# PicoLED.net
KiCad netlist of a schematic drawn in EasyEDA Pro
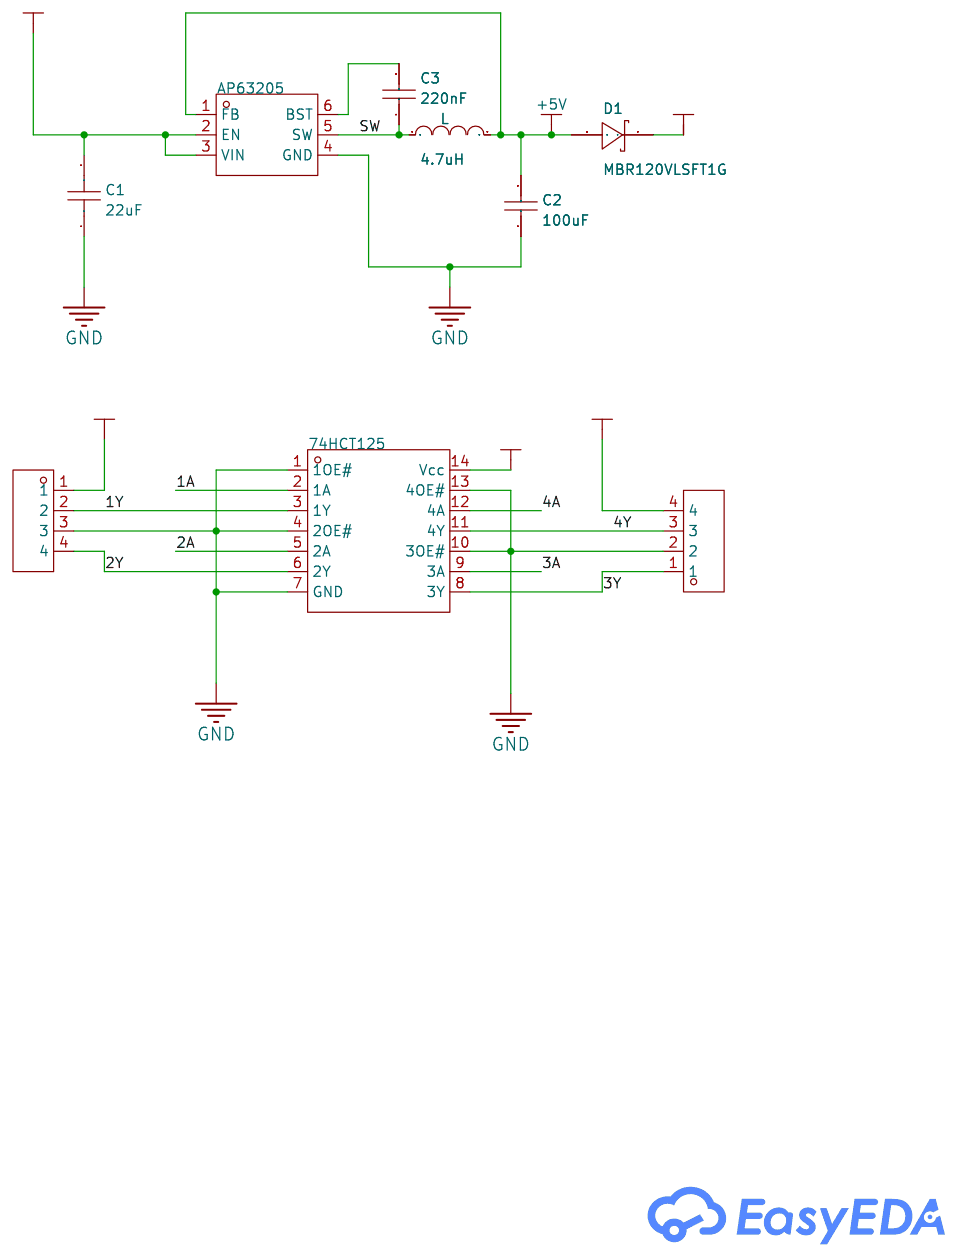
[diagram p0: schematic sheet]

(export (version "E")
  (design (tool "Eeschema 10.0.6"))
  (components
    (comp (ref "74HCT125")
      (value "74HCT125T14-13")
      (footprint "easyedapro:TSSOP-14_L5.0-W4.4-P0.65-LS6.4-BL")
      (fields (field (name "Manufacturer") "DIODES(美台)"))
      (libsource (lib "easyedapro") (part "74HCT125T14-13"))
    )
    (comp (ref "AP63205")
      (value "AP63205WU-7")
      (footprint "easyedapro:TSOT-23-6_L2.9-W1.6-P0.95-LS2.8-BL")
      (fields (field (name "Manufacturer") "DIODES(美台)"))
      (libsource (lib "easyedapro") (part "AP63205WU-7"))
    )
    (comp (ref "C1")
      (value "22uF")
      (footprint "easyedapro:C1210")
      (fields
        (field (name "Manufacturer Part") "GMK325BJ226MM-P")
        (field (name "Manufacturer") "TAIYO YUDEN(太诱)")
      )
      (libsource (lib "easyedapro") (part "GMK325BJ226MM-P"))
    )
    (comp (ref "C2")
      (value "100uF")
      (footprint "easyedapro:C1210")
      (fields
        (field (name "Manufacturer Part") "CL32A107MQVNNNE")
        (field (name "Manufacturer") "SAMSUNG(三星)")
      )
      (libsource (lib "easyedapro") (part "CL32A107MQVNNNE"))
    )
    (comp (ref "C3")
      (value "220nF")
      (footprint "easyedapro:C0603")
      (fields
        (field (name "Manufacturer Part") "CL10B224KB8NNNC")
        (field (name "Manufacturer") "SAMSUNG(三星)")
      )
      (libsource (lib "easyedapro") (part "CL10B224KB8NNNC"))
    )
    (comp (ref "CN1")
      (value "DB125-3.5-4P-GN-S")
      (footprint "easyedapro:CONN-TH_DB125-3.5-4P-GN")
      (fields (field (name "Manufacturer") "DORABO(地博电气)"))
      (libsource (lib "easyedapro") (part "DB125-3.5-4P-GN"))
    )
    (comp (ref "CN2")
      (value "DB125-3.5-4P-GN-S")
      (footprint "easyedapro:CONN-TH_DB125-3.5-4P-GN")
      (fields (field (name "Manufacturer") "DORABO(地博电气)"))
      (libsource (lib "easyedapro") (part "DB125-3.5-4P-GN"))
    )
    (comp (ref "D1")
      (value "MBR120VLSFT1G")
      (footprint "easyedapro:SOD-123F_L2.8-W1.8-LS3.7-RD")
      (fields (field (name "Manufacturer") "onsemi(安森美)"))
      (libsource (lib "easyedapro") (part "MBR120VLSFT1G"))
    )
    (comp (ref "L")
      (value "4.7uH")
      (footprint "easyedapro:IND-SMD_L4.0-W4.0")
      (fields (field (name "Manufacturer Part") "CR4030-4R7M") (field (name "Manufacturer") "ceaiya(柯爱亚)"))
      (libsource (lib "easyedapro") (part "CR4030-4R7M"))
    )
  )
  (nets
    (net (code "1") (name "+5V") (class "Default")
      (node (ref "AP63205") (pin "1") (pinfunction "FB_1") (pintype "unspecified"))
      (node (ref "C2") (pin "2") (pinfunction "2_2") (pintype "input"))
      (node (ref "D1") (pin "2") (pinfunction "A_2") (pintype "unspecified"))
      (node (ref "L") (pin "2") (pinfunction "2_2") (pintype "unspecified"))
    )
    (net (code "2") (name "/1A") (class "Default")
      (node (ref "74HCT125") (pin "2") (pinfunction "1A_2") (pintype "unspecified"))
    )
    (net (code "3") (name "/1Y") (class "Default")
      (node (ref "74HCT125") (pin "3") (pinfunction "1Y_3") (pintype "unspecified"))
      (node (ref "CN1") (pin "2") (pinfunction "2_2") (pintype "unspecified"))
    )
    (net (code "4") (name "/2A") (class "Default")
      (node (ref "74HCT125") (pin "5") (pinfunction "2A_5") (pintype "unspecified"))
    )
    (net (code "5") (name "/2Y") (class "Default")
      (node (ref "74HCT125") (pin "6") (pinfunction "2Y_6") (pintype "unspecified"))
      (node (ref "CN1") (pin "4") (pinfunction "4_4") (pintype "unspecified"))
    )
    (net (code "6") (name "/3A") (class "Default")
      (node (ref "74HCT125") (pin "9") (pinfunction "3A_9") (pintype "unspecified"))
    )
    (net (code "7") (name "/3Y") (class "Default")
      (node (ref "74HCT125") (pin "8") (pinfunction "3Y_8") (pintype "unspecified"))
      (node (ref "CN2") (pin "1") (pinfunction "1_1") (pintype "unspecified"))
    )
    (net (code "8") (name "/4A") (class "Default")
      (node (ref "74HCT125") (pin "12") (pinfunction "4A_12") (pintype "unspecified"))
    )
    (net (code "9") (name "/4Y") (class "Default")
      (node (ref "74HCT125") (pin "11") (pinfunction "4Y_11") (pintype "unspecified"))
      (node (ref "CN2") (pin "3") (pinfunction "3_3") (pintype "unspecified"))
    )
    (net (code "10") (name "/SW") (class "Default")
      (node (ref "AP63205") (pin "5") (pinfunction "SW_5") (pintype "unspecified"))
      (node (ref "C3") (pin "1") (pinfunction "1_1") (pintype "input"))
      (node (ref "L") (pin "1") (pinfunction "1_1") (pintype "unspecified"))
    )
    (net (code "11") (name "GND") (class "Default")
      (node (ref "74HCT125") (pin "1") (pinfunction "1OE#_1") (pintype "unspecified"))
      (node (ref "74HCT125") (pin "10") (pinfunction "3OE#_10") (pintype "unspecified"))
      (node (ref "74HCT125") (pin "13") (pinfunction "4OE#_13") (pintype "unspecified"))
      (node (ref "74HCT125") (pin "4") (pinfunction "2OE#_4") (pintype "unspecified"))
      (node (ref "74HCT125") (pin "7") (pinfunction "GND_7") (pintype "unspecified"))
      (node (ref "AP63205") (pin "4") (pinfunction "GND_4") (pintype "unspecified"))
      (node (ref "C1") (pin "1") (pinfunction "1_1") (pintype "unspecified"))
      (node (ref "C2") (pin "1") (pinfunction "1_1") (pintype "input"))
      (node (ref "CN1") (pin "3") (pinfunction "3_3") (pintype "unspecified"))
      (node (ref "CN2") (pin "2") (pinfunction "2_2") (pintype "unspecified"))
    )
    (net (code "12") (name "Net-(AP63205-BST)") (class "Default")
      (node (ref "AP63205") (pin "6") (pinfunction "BST_6") (pintype "unspecified"))
      (node (ref "C3") (pin "2") (pinfunction "2_2") (pintype "input"))
    )
    (net (code "13") (name "VIN") (class "Default")
      (node (ref "AP63205") (pin "2") (pinfunction "EN_2") (pintype "unspecified"))
      (node (ref "AP63205") (pin "3") (pinfunction "VIN_3") (pintype "unspecified"))
      (node (ref "C1") (pin "2") (pinfunction "2_2") (pintype "unspecified"))
      (node (ref "CN1") (pin "1") (pinfunction "1_1") (pintype "unspecified"))
      (node (ref "CN2") (pin "4") (pinfunction "4_4") (pintype "unspecified"))
    )
    (net (code "14") (name "VSYS") (class "Default")
      (node (ref "74HCT125") (pin "14") (pinfunction "Vcc_14") (pintype "unspecified"))
      (node (ref "D1") (pin "1") (pinfunction "K_1") (pintype "unspecified"))
    )
  )
)
